# placa_conexoes.net
KiCad netlist of a schematic drawn in EAGLE
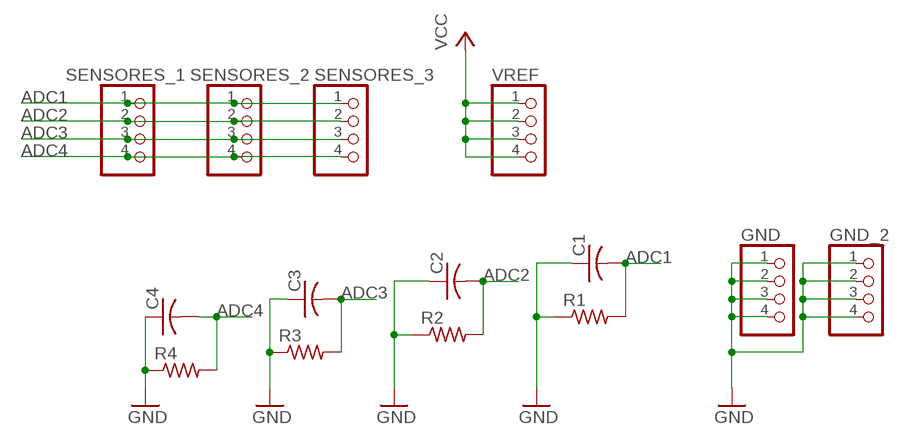
[diagram p0: schematic, sheet 1]

(export (version "E")
  (design (tool "Eeschema 10.0.6"))
  (components
    (comp (ref "C1")
      (value "C-US025-025X050")
      (footprint "eagle-import:C025-025X050")
      (libsource (lib "eagle-import") (part "C-US025-025X050"))
    )
    (comp (ref "C2")
      (value "C-US025-025X050")
      (footprint "eagle-import:C025-025X050")
      (libsource (lib "eagle-import") (part "C-US025-025X050"))
    )
    (comp (ref "C3")
      (value "C-US025-025X050")
      (footprint "eagle-import:C025-025X050")
      (libsource (lib "eagle-import") (part "C-US025-025X050"))
    )
    (comp (ref "C4")
      (value "C-US025-025X050")
      (footprint "eagle-import:C025-025X050")
      (libsource (lib "eagle-import") (part "C-US025-025X050"))
    )
    (comp (ref "GND")
      (value "PINHD-1X4")
      (footprint "eagle-import:1X04")
      (libsource (lib "eagle-import") (part "PINHD-1X4"))
    )
    (comp (ref "GND_2")
      (value "PINHD-1X4")
      (footprint "eagle-import:1X04")
      (libsource (lib "eagle-import") (part "PINHD-1X4"))
    )
    (comp (ref "R1")
      (value "R-US_0207/9")
      (footprint "eagle-import:0207_9")
      (libsource (lib "eagle-import") (part "R-US_0207/9"))
    )
    (comp (ref "R2")
      (value "R-US_0207/9")
      (footprint "eagle-import:0207_9")
      (libsource (lib "eagle-import") (part "R-US_0207/9"))
    )
    (comp (ref "R3")
      (value "R-US_0207/9")
      (footprint "eagle-import:0207_9")
      (libsource (lib "eagle-import") (part "R-US_0207/9"))
    )
    (comp (ref "R4")
      (value "R-US_0207/9")
      (footprint "eagle-import:0207_9")
      (libsource (lib "eagle-import") (part "R-US_0207/9"))
    )
    (comp (ref "SENSORES_1")
      (value "PINHD-1X4")
      (footprint "eagle-import:1X04")
      (libsource (lib "eagle-import") (part "PINHD-1X4"))
    )
    (comp (ref "SENSORES_2")
      (value "PINHD-1X4")
      (footprint "eagle-import:1X04")
      (libsource (lib "eagle-import") (part "PINHD-1X4"))
    )
    (comp (ref "SENSORES_3")
      (value "PINHD-1X4")
      (footprint "eagle-import:1X04")
      (libsource (lib "eagle-import") (part "PINHD-1X4"))
    )
    (comp (ref "VREF")
      (value "PINHD-1X4")
      (footprint "eagle-import:1X04")
      (libsource (lib "eagle-import") (part "PINHD-1X4"))
    )
  )
  (nets
    (net (code "1") (name "/ADC1") (class "Default")
      (node (ref "C1") (pin "2") (pinfunction "2_2") (pintype "passive"))
      (node (ref "R1") (pin "2") (pinfunction "2_2") (pintype "passive"))
      (node (ref "SENSORES_1") (pin "1") (pinfunction "1_1") (pintype "passive"))
      (node (ref "SENSORES_2") (pin "1") (pinfunction "1_1") (pintype "passive"))
      (node (ref "SENSORES_3") (pin "1") (pinfunction "1_1") (pintype "passive"))
    )
    (net (code "2") (name "/ADC2") (class "Default")
      (node (ref "C2") (pin "2") (pinfunction "2_2") (pintype "passive"))
      (node (ref "R2") (pin "2") (pinfunction "2_2") (pintype "passive"))
      (node (ref "SENSORES_1") (pin "2") (pinfunction "2_2") (pintype "passive"))
      (node (ref "SENSORES_2") (pin "2") (pinfunction "2_2") (pintype "passive"))
      (node (ref "SENSORES_3") (pin "2") (pinfunction "2_2") (pintype "passive"))
    )
    (net (code "3") (name "/ADC3") (class "Default")
      (node (ref "C3") (pin "2") (pinfunction "2_2") (pintype "passive"))
      (node (ref "R3") (pin "2") (pinfunction "2_2") (pintype "passive"))
      (node (ref "SENSORES_1") (pin "3") (pinfunction "3_3") (pintype "passive"))
      (node (ref "SENSORES_2") (pin "3") (pinfunction "3_3") (pintype "passive"))
      (node (ref "SENSORES_3") (pin "3") (pinfunction "3_3") (pintype "passive"))
    )
    (net (code "4") (name "/ADC4") (class "Default")
      (node (ref "C4") (pin "2") (pinfunction "2_2") (pintype "passive"))
      (node (ref "R4") (pin "2") (pinfunction "2_2") (pintype "passive"))
      (node (ref "SENSORES_1") (pin "4") (pinfunction "4_4") (pintype "passive"))
      (node (ref "SENSORES_2") (pin "4") (pinfunction "4_4") (pintype "passive"))
      (node (ref "SENSORES_3") (pin "4") (pinfunction "4_4") (pintype "passive"))
    )
    (net (code "5") (name "GND") (class "Default")
      (node (ref "C1") (pin "1") (pinfunction "1_1") (pintype "passive"))
      (node (ref "C2") (pin "1") (pinfunction "1_1") (pintype "passive"))
      (node (ref "C3") (pin "1") (pinfunction "1_1") (pintype "passive"))
      (node (ref "C4") (pin "1") (pinfunction "1_1") (pintype "passive"))
      (node (ref "GND") (pin "1") (pinfunction "1_1") (pintype "passive"))
      (node (ref "GND") (pin "2") (pinfunction "2_2") (pintype "passive"))
      (node (ref "GND") (pin "3") (pinfunction "3_3") (pintype "passive"))
      (node (ref "GND") (pin "4") (pinfunction "4_4") (pintype "passive"))
      (node (ref "GND_2") (pin "1") (pinfunction "1_1") (pintype "passive"))
      (node (ref "GND_2") (pin "2") (pinfunction "2_2") (pintype "passive"))
      (node (ref "GND_2") (pin "3") (pinfunction "3_3") (pintype "passive"))
      (node (ref "GND_2") (pin "4") (pinfunction "4_4") (pintype "passive"))
      (node (ref "R1") (pin "1") (pinfunction "1_1") (pintype "passive"))
      (node (ref "R2") (pin "1") (pinfunction "1_1") (pintype "passive"))
      (node (ref "R3") (pin "1") (pinfunction "1_1") (pintype "passive"))
      (node (ref "R4") (pin "1") (pinfunction "1_1") (pintype "passive"))
    )
    (net (code "6") (name "VCC") (class "Default")
      (node (ref "VREF") (pin "1") (pinfunction "1_1") (pintype "passive"))
      (node (ref "VREF") (pin "2") (pinfunction "2_2") (pintype "passive"))
      (node (ref "VREF") (pin "3") (pinfunction "3_3") (pintype "passive"))
      (node (ref "VREF") (pin "4") (pinfunction "4_4") (pintype "passive"))
    )
  )
)
